# DAU_Kupplung_3phasig_Basisstation_V1_2.net
KiCad netlist of a schematic drawn in EAGLE
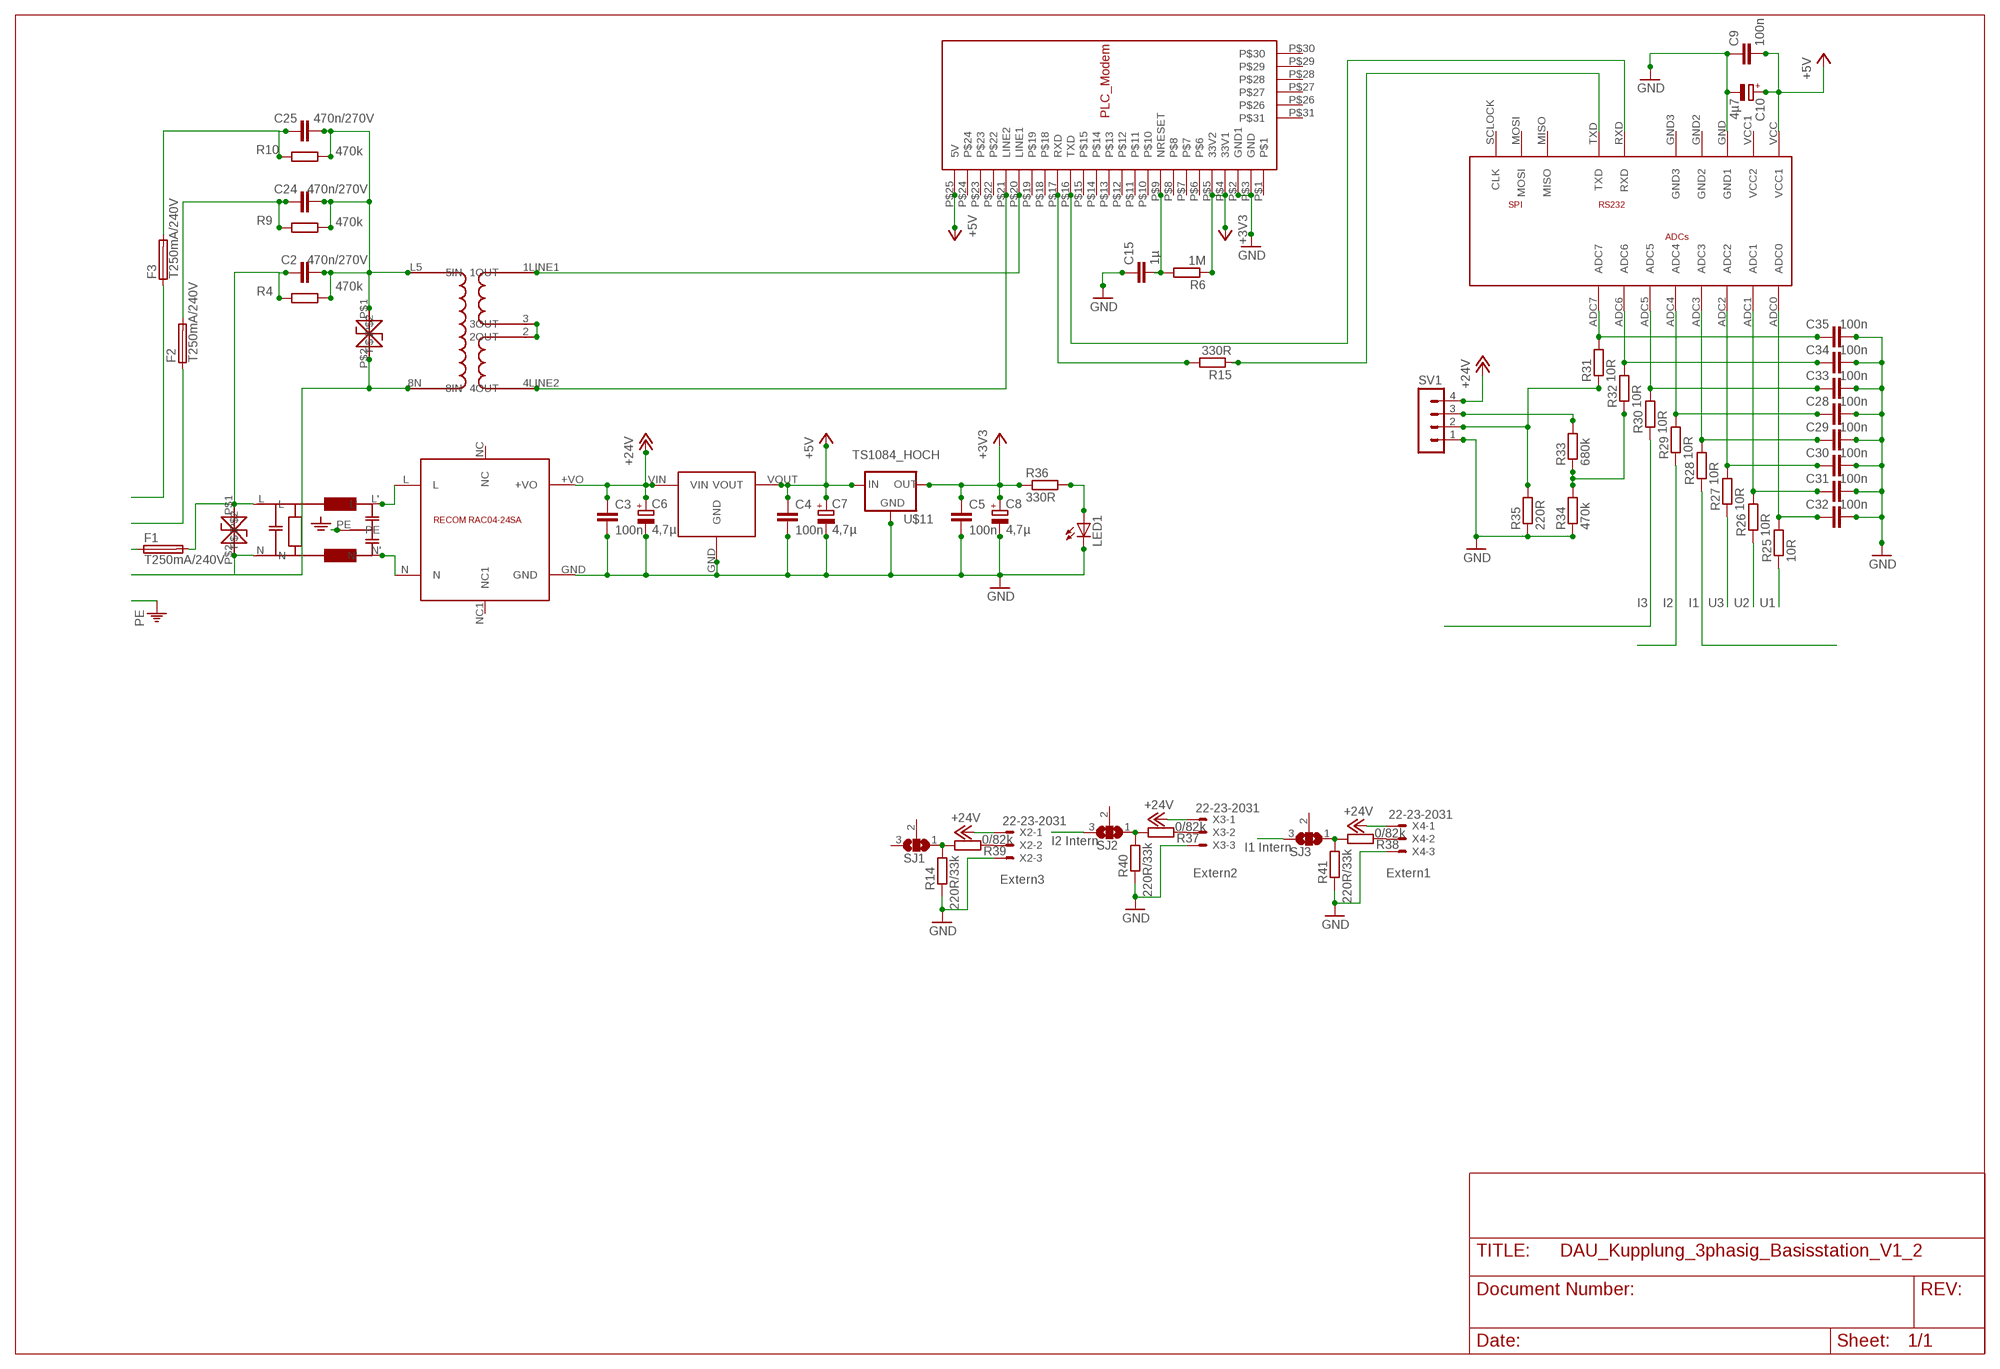
[diagram p0: schematic, sheet 1]

(export (version "E")
  (design (tool "Eeschema 10.0.6"))
  (components
    (comp (ref "C2")
      (value "470n/270V")
      (footprint "eagle-import:C225-087X268")
      (libsource (lib "eagle-import") (part "C-EU225-087X268"))
    )
    (comp (ref "C3")
      (value "100n")
      (footprint "eagle-import:C0805K")
      (libsource (lib "eagle-import") (part "C-EUC0805K"))
    )
    (comp (ref "C4")
      (value "100n")
      (footprint "eagle-import:C0805K")
      (libsource (lib "eagle-import") (part "C-EUC0805K"))
    )
    (comp (ref "C5")
      (value "100n")
      (footprint "eagle-import:C0805K")
      (libsource (lib "eagle-import") (part "C-EUC0805K"))
    )
    (comp (ref "C6")
      (value "4,7µ")
      (footprint "eagle-import:E2,5-6")
      (libsource (lib "eagle-import") (part "resistor_CPOL-EUE2.5-6"))
    )
    (comp (ref "C7")
      (value "4,7µ")
      (footprint "eagle-import:E2,5-6")
      (libsource (lib "eagle-import") (part "resistor_CPOL-EUE2.5-6"))
    )
    (comp (ref "C8")
      (value "4,7µ")
      (footprint "eagle-import:E2,5-6")
      (libsource (lib "eagle-import") (part "resistor_CPOL-EUE2.5-6"))
    )
    (comp (ref "C9")
      (value "100n")
      (footprint "eagle-import:C0805K")
      (libsource (lib "eagle-import") (part "C-EUC0805K"))
    )
    (comp (ref "C10")
      (value "4µ7")
      (footprint "eagle-import:E2,5-6E")
      (libsource (lib "eagle-import") (part "CPOL-EUE2,5-6E"))
    )
    (comp (ref "C15")
      (value "1µ")
      (footprint "eagle-import:C0805K")
      (libsource (lib "eagle-import") (part "C-EUC0805K"))
    )
    (comp (ref "C24")
      (value "470n/270V")
      (footprint "eagle-import:C225-087X268")
      (libsource (lib "eagle-import") (part "C-EU225-087X268"))
    )
    (comp (ref "C25")
      (value "470n/270V")
      (footprint "eagle-import:C225-087X268")
      (libsource (lib "eagle-import") (part "C-EU225-087X268"))
    )
    (comp (ref "C28")
      (value "100n")
      (footprint "eagle-import:C0805K")
      (libsource (lib "eagle-import") (part "C-EUC0805K"))
    )
    (comp (ref "C29")
      (value "100n")
      (footprint "eagle-import:C0805K")
      (libsource (lib "eagle-import") (part "C-EUC0805K"))
    )
    (comp (ref "C30")
      (value "100n")
      (footprint "eagle-import:C0805K")
      (libsource (lib "eagle-import") (part "C-EUC0805K"))
    )
    (comp (ref "C31")
      (value "100n")
      (footprint "eagle-import:C0805K")
      (libsource (lib "eagle-import") (part "C-EUC0805K"))
    )
    (comp (ref "C32")
      (value "100n")
      (footprint "eagle-import:C0805K")
      (libsource (lib "eagle-import") (part "C-EUC0805K"))
    )
    (comp (ref "C33")
      (value "100n")
      (footprint "eagle-import:C0805K")
      (libsource (lib "eagle-import") (part "C-EUC0805K"))
    )
    (comp (ref "C34")
      (value "100n")
      (footprint "eagle-import:C0805K")
      (libsource (lib "eagle-import") (part "C-EUC0805K"))
    )
    (comp (ref "C35")
      (value "100n")
      (footprint "eagle-import:C0805K")
      (libsource (lib "eagle-import") (part "C-EUC0805K"))
    )
    (comp (ref "F1")
      (value "T250mA/240V")
      (footprint "eagle-import:TR5")
      (libsource (lib "eagle-import") (part "TR5"))
    )
    (comp (ref "F2")
      (value "T250mA/240V")
      (footprint "eagle-import:TR5")
      (fields (field (name "OC_FARNELL") "unknown") (field (name "OC_NEWARK") "unknown"))
      (libsource (lib "eagle-import") (part "TR5"))
    )
    (comp (ref "F3")
      (value "T250mA/240V")
      (footprint "eagle-import:TR5")
      (fields (field (name "OC_FARNELL") "unknown") (field (name "OC_NEWARK") "unknown"))
      (libsource (lib "eagle-import") (part "TR5"))
    )
    (comp (ref "LED1")
      (value "LEDSQR2X5")
      (footprint "eagle-import:LED2X5")
      (libsource (lib "eagle-import") (part "LEDSQR2X5"))
    )
    (comp (ref "P6KE300CA")
      (value "P6KE300CA")
      (footprint "eagle-import:TSV")
      (libsource (lib "eagle-import") (part "TSV"))
    )
    (comp (ref "R4")
      (value "470k")
      (footprint "eagle-import:0204_7")
      (libsource (lib "eagle-import") (part "R-EU_0204/7"))
    )
    (comp (ref "R6")
      (value "1M")
      (footprint "eagle-import:R0805")
      (libsource (lib "eagle-import") (part "R-EU_R0805"))
    )
    (comp (ref "R9")
      (value "470k")
      (footprint "eagle-import:0204_7")
      (libsource (lib "eagle-import") (part "R-EU_0204/7"))
    )
    (comp (ref "R10")
      (value "470k")
      (footprint "eagle-import:0204_7")
      (libsource (lib "eagle-import") (part "R-EU_0204/7"))
    )
    (comp (ref "R14")
      (value "220R/33k")
      (footprint "eagle-import:R0805")
      (libsource (lib "eagle-import") (part "R-EU_R0805"))
    )
    (comp (ref "R15")
      (value "330R")
      (footprint "eagle-import:R0805")
      (libsource (lib "eagle-import") (part "R-EU_R0805"))
    )
    (comp (ref "R25")
      (value "10R")
      (footprint "eagle-import:R0805")
      (libsource (lib "eagle-import") (part "R-EU_R0805"))
    )
    (comp (ref "R26")
      (value "10R")
      (footprint "eagle-import:R0805")
      (libsource (lib "eagle-import") (part "R-EU_R0805"))
    )
    (comp (ref "R27")
      (value "10R")
      (footprint "eagle-import:R0805")
      (libsource (lib "eagle-import") (part "R-EU_R0805"))
    )
    (comp (ref "R28")
      (value "10R")
      (footprint "eagle-import:R0805")
      (libsource (lib "eagle-import") (part "R-EU_R0805"))
    )
    (comp (ref "R29")
      (value "10R")
      (footprint "eagle-import:R0805")
      (libsource (lib "eagle-import") (part "R-EU_R0805"))
    )
    (comp (ref "R30")
      (value "10R")
      (footprint "eagle-import:R0805")
      (libsource (lib "eagle-import") (part "R-EU_R0805"))
    )
    (comp (ref "R31")
      (value "10R")
      (footprint "eagle-import:R0805")
      (libsource (lib "eagle-import") (part "R-EU_R0805"))
    )
    (comp (ref "R32")
      (value "10R")
      (footprint "eagle-import:R0805")
      (libsource (lib "eagle-import") (part "R-EU_R0805"))
    )
    (comp (ref "R33")
      (value "680k")
      (footprint "eagle-import:R0805")
      (libsource (lib "eagle-import") (part "R-EU_R0805"))
    )
    (comp (ref "R34")
      (value "470k")
      (footprint "eagle-import:R0805")
      (libsource (lib "eagle-import") (part "R-EU_R0805"))
    )
    (comp (ref "R35")
      (value "220R")
      (footprint "eagle-import:R0805")
      (libsource (lib "eagle-import") (part "R-EU_R0805"))
    )
    (comp (ref "R36")
      (value "330R")
      (footprint "eagle-import:R0805")
      (libsource (lib "eagle-import") (part "R-EU_R0805"))
    )
    (comp (ref "R37")
      (value "0/82k")
      (footprint "eagle-import:R0805")
      (libsource (lib "eagle-import") (part "R-EU_R0805"))
    )
    (comp (ref "R38")
      (value "0/82k")
      (footprint "eagle-import:R0805")
      (libsource (lib "eagle-import") (part "R-EU_R0805"))
    )
    (comp (ref "R39")
      (value "0/82k")
      (footprint "eagle-import:R0805")
      (libsource (lib "eagle-import") (part "R-EU_R0805"))
    )
    (comp (ref "R40")
      (value "220R/33k")
      (footprint "eagle-import:R0805")
      (libsource (lib "eagle-import") (part "R-EU_R0805"))
    )
    (comp (ref "R41")
      (value "220R/33k")
      (footprint "eagle-import:R0805")
      (libsource (lib "eagle-import") (part "R-EU_R0805"))
    )
    (comp (ref "SJ1")
      (value "SJ2WW")
      (footprint "eagle-import:SJ_2W")
      (libsource (lib "eagle-import") (part "SJ2WW"))
    )
    (comp (ref "SJ2")
      (value "SJ2WW")
      (footprint "eagle-import:SJ_2W")
      (libsource (lib "eagle-import") (part "SJ2WW"))
    )
    (comp (ref "SJ3")
      (value "SJ2WW")
      (footprint "eagle-import:SJ_2W")
      (libsource (lib "eagle-import") (part "SJ2WW"))
    )
    (comp (ref "SV1")
      (value "MA04-1")
      (footprint "eagle-import:MA04-1")
      (libsource (lib "eagle-import") (part "MA04-1"))
    )
    (comp (ref "TSV2")
      (value "TSV")
      (footprint "eagle-import:TSV")
      (libsource (lib "eagle-import") (part "TSV"))
    )
    (comp (ref "U$1")
      (value "RECOM_RAC04_24SA")
      (footprint "eagle-import:RAC04_12SA")
      (libsource (lib "eagle-import") (part "RECOM_RAC04_24SA"))
    )
    (comp (ref "U$3")
      (value "ADUC831_MINIMUM")
      (footprint "eagle-import:ADUC_MINIMUM")
      (libsource (lib "eagle-import") (part "ADUC831_MINIMUM"))
    )
    (comp (ref "U$4")
      (value "MODEMSTECKER")
      (footprint "eagle-import:MODEM_FUSS")
      (libsource (lib "eagle-import") (part "MODEMSTECKER"))
    )
    (comp (ref "U$5")
      (value "PLC_UEBERTRAGER_V2")
      (footprint "eagle-import:PLC-UEBERTRAGER_V2")
      (libsource (lib "eagle-import") (part "PLC_UEBERTRAGER_V2"))
    )
    (comp (ref "U$10")
      (value "RECOM_785_05")
      (footprint "eagle-import:RECOM785X")
      (libsource (lib "eagle-import") (part "RECOM_785_05"))
    )
    (comp (ref "U$11")
      (value "TS1084_HOCH")
      (footprint "eagle-import:TS1084_HOCH")
      (libsource (lib "eagle-import") (part "TS1084_HOCH"))
    )
    (comp (ref "U$20")
      (value "NETZFILTER_05_A")
      (footprint "eagle-import:NETZFILTER")
      (libsource (lib "eagle-import") (part "NETZFILTER_05_A"))
    )
    (comp (ref "X2")
      (value "22-23-2031")
      (footprint "eagle-import:22-23-2031")
      (fields (field (name "MF") "MOLEX"))
      (libsource (lib "eagle-import") (part "22-23-2031"))
    )
    (comp (ref "X3")
      (value "22-23-2031")
      (footprint "eagle-import:22-23-2031")
      (fields (field (name "MF") "MOLEX"))
      (libsource (lib "eagle-import") (part "22-23-2031"))
    )
    (comp (ref "X4")
      (value "22-23-2031")
      (footprint "eagle-import:22-23-2031")
      (fields (field (name "MF") "MOLEX"))
      (libsource (lib "eagle-import") (part "22-23-2031"))
    )
  )
  (nets
    (net (code "1") (name "+3V3") (class "Default")
      (node (ref "C5") (pin "1") (pinfunction "1_1") (pintype "passive"))
      (node (ref "C8") (pin "+") (pinfunction "+_+") (pintype "passive"))
      (node (ref "R36") (pin "1") (pinfunction "1_1") (pintype "passive"))
      (node (ref "R6") (pin "1") (pinfunction "1_1") (pintype "passive"))
      (node (ref "U$11") (pin "OUT") (pinfunction "OUT_OUT") (pintype "passive"))
      (node (ref "U$4") (pin "P$4") (pinfunction "33V1_P$4") (pintype "bidirectional"))
      (node (ref "U$4") (pin "P$5") (pinfunction "33V2_P$5") (pintype "bidirectional"))
    )
    (net (code "2") (name "+5V") (class "Default")
      (node (ref "C10") (pin "+") (pinfunction "+_+") (pintype "passive"))
      (node (ref "C4") (pin "1") (pinfunction "1_1") (pintype "passive"))
      (node (ref "C7") (pin "+") (pinfunction "+_+") (pintype "passive"))
      (node (ref "C9") (pin "2") (pinfunction "2_2") (pintype "passive"))
      (node (ref "U$10") (pin "VOUT") (pinfunction "VOUT_VOUT") (pintype "bidirectional"))
      (node (ref "U$11") (pin "IN") (pinfunction "IN_IN") (pintype "input"))
      (node (ref "U$3") (pin "VCC") (pinfunction "VCC1_VCC") (pintype "bidirectional"))
      (node (ref "U$4") (pin "P$25") (pinfunction "5V_P$25") (pintype "bidirectional"))
    )
    (net (code "3") (name "+24V") (class "Default")
      (node (ref "C3") (pin "1") (pinfunction "1_1") (pintype "passive"))
      (node (ref "C6") (pin "+") (pinfunction "+_+") (pintype "passive"))
      (node (ref "SV1") (pin "4") (pinfunction "4_4") (pintype "passive"))
      (node (ref "U$1") (pin "+VO") (pinfunction "+VO_+VO") (pintype "bidirectional"))
      (node (ref "U$10") (pin "VIN") (pinfunction "VIN_VIN") (pintype "bidirectional"))
      (node (ref "X2") (pin "1") (pinfunction "S_1") (pintype "passive"))
      (node (ref "X3") (pin "1") (pinfunction "S_1") (pintype "passive"))
      (node (ref "X4") (pin "1") (pinfunction "S_1") (pintype "passive"))
    )
    (net (code "4") (name "/L1") (class "Default")
      (node (ref "C2") (pin "1") (pinfunction "1_1") (pintype "passive"))
      (node (ref "F1") (pin "2") (pinfunction "2_2") (pintype "passive"))
      (node (ref "P6KE300CA") (pin "P$1") (pinfunction "P$1_P$1") (pintype "bidirectional"))
      (node (ref "R4") (pin "2") (pinfunction "2_2") (pintype "passive"))
      (node (ref "U$20") (pin "L") (pinfunction "L_L") (pintype "bidirectional"))
    )
    (net (code "5") (name "GND") (class "Default")
      (node (ref "C10") (pin "-") (pinfunction "-_-") (pintype "passive"))
      (node (ref "C15") (pin "1") (pinfunction "1_1") (pintype "passive"))
      (node (ref "C28") (pin "2") (pinfunction "2_2") (pintype "passive"))
      (node (ref "C29") (pin "2") (pinfunction "2_2") (pintype "passive"))
      (node (ref "C3") (pin "2") (pinfunction "2_2") (pintype "passive"))
      (node (ref "C30") (pin "2") (pinfunction "2_2") (pintype "passive"))
      (node (ref "C31") (pin "2") (pinfunction "2_2") (pintype "passive"))
      (node (ref "C32") (pin "2") (pinfunction "2_2") (pintype "passive"))
      (node (ref "C33") (pin "2") (pinfunction "2_2") (pintype "passive"))
      (node (ref "C34") (pin "2") (pinfunction "2_2") (pintype "passive"))
      (node (ref "C35") (pin "2") (pinfunction "2_2") (pintype "passive"))
      (node (ref "C4") (pin "2") (pinfunction "2_2") (pintype "passive"))
      (node (ref "C5") (pin "2") (pinfunction "2_2") (pintype "passive"))
      (node (ref "C6") (pin "-") (pinfunction "-_-") (pintype "passive"))
      (node (ref "C7") (pin "-") (pinfunction "-_-") (pintype "passive"))
      (node (ref "C8") (pin "-") (pinfunction "-_-") (pintype "passive"))
      (node (ref "C9") (pin "1") (pinfunction "1_1") (pintype "passive"))
      (node (ref "LED1") (pin "K") (pinfunction "C_K") (pintype "passive"))
      (node (ref "R14") (pin "1") (pinfunction "1_1") (pintype "passive"))
      (node (ref "R34") (pin "1") (pinfunction "1_1") (pintype "passive"))
      (node (ref "R35") (pin "1") (pinfunction "1_1") (pintype "passive"))
      (node (ref "R40") (pin "1") (pinfunction "1_1") (pintype "passive"))
      (node (ref "R41") (pin "1") (pinfunction "1_1") (pintype "passive"))
      (node (ref "SV1") (pin "1") (pinfunction "1_1") (pintype "passive"))
      (node (ref "U$1") (pin "GND") (pinfunction "GND_GND") (pintype "bidirectional"))
      (node (ref "U$10") (pin "GND") (pinfunction "GND_GND") (pintype "bidirectional"))
      (node (ref "U$11") (pin "GND") (pinfunction "GND_GND") (pintype "input"))
      (node (ref "U$3") (pin "GND") (pinfunction "GND1_GND") (pintype "bidirectional"))
      (node (ref "U$4") (pin "P$2") (pinfunction "GND1_P$2") (pintype "bidirectional"))
      (node (ref "U$4") (pin "P$3") (pinfunction "GND_P$3") (pintype "bidirectional"))
      (node (ref "X2") (pin "3") (pinfunction "S_3") (pintype "passive"))
      (node (ref "X3") (pin "3") (pinfunction "S_3") (pintype "passive"))
      (node (ref "X4") (pin "3") (pinfunction "S_3") (pintype "passive"))
    )
    (net (code "6") (name "Net-(C24-Pad1)") (class "Default")
      (node (ref "C24") (pin "1") (pinfunction "1_1") (pintype "passive"))
      (node (ref "F2") (pin "2") (pinfunction "2_2") (pintype "passive"))
      (node (ref "R9") (pin "2") (pinfunction "2_2") (pintype "passive"))
    )
    (net (code "7") (name "Net-(C25-Pad1)") (class "Default")
      (node (ref "C25") (pin "1") (pinfunction "1_1") (pintype "passive"))
      (node (ref "F3") (pin "2") (pinfunction "2_2") (pintype "passive"))
      (node (ref "R10") (pin "2") (pinfunction "2_2") (pintype "passive"))
    )
    (net (code "8") (name "Net-(C28-Pad1)") (class "Default")
      (node (ref "C28") (pin "1") (pinfunction "1_1") (pintype "passive"))
      (node (ref "R29") (pin "2") (pinfunction "2_2") (pintype "passive"))
      (node (ref "U$3") (pin "ADC4") (pinfunction "ADC4_ADC4") (pintype "bidirectional"))
    )
    (net (code "9") (name "Net-(C29-Pad1)") (class "Default")
      (node (ref "C29") (pin "1") (pinfunction "1_1") (pintype "passive"))
      (node (ref "R28") (pin "2") (pinfunction "2_2") (pintype "passive"))
      (node (ref "U$3") (pin "ADC3") (pinfunction "ADC3_ADC3") (pintype "bidirectional"))
    )
    (net (code "10") (name "Net-(C30-Pad1)") (class "Default")
      (node (ref "C30") (pin "1") (pinfunction "1_1") (pintype "passive"))
      (node (ref "R27") (pin "2") (pinfunction "2_2") (pintype "passive"))
      (node (ref "U$3") (pin "ADC2") (pinfunction "ADC2_ADC2") (pintype "bidirectional"))
    )
    (net (code "11") (name "Net-(C31-Pad1)") (class "Default")
      (node (ref "C31") (pin "1") (pinfunction "1_1") (pintype "passive"))
      (node (ref "R26") (pin "2") (pinfunction "2_2") (pintype "passive"))
      (node (ref "U$3") (pin "ADC1") (pinfunction "ADC1_ADC1") (pintype "bidirectional"))
    )
    (net (code "12") (name "Net-(C32-Pad1)") (class "Default")
      (node (ref "C32") (pin "1") (pinfunction "1_1") (pintype "passive"))
      (node (ref "R25") (pin "2") (pinfunction "2_2") (pintype "passive"))
      (node (ref "U$3") (pin "ADC0") (pinfunction "ADC0_ADC0") (pintype "bidirectional"))
    )
    (net (code "13") (name "Net-(C33-Pad1)") (class "Default")
      (node (ref "C33") (pin "1") (pinfunction "1_1") (pintype "passive"))
      (node (ref "R30") (pin "2") (pinfunction "2_2") (pintype "passive"))
      (node (ref "U$3") (pin "ADC5") (pinfunction "ADC5_ADC5") (pintype "bidirectional"))
    )
    (net (code "14") (name "Net-(C34-Pad1)") (class "Default")
      (node (ref "C34") (pin "1") (pinfunction "1_1") (pintype "passive"))
      (node (ref "R32") (pin "2") (pinfunction "2_2") (pintype "passive"))
      (node (ref "U$3") (pin "ADC6") (pinfunction "ADC6_ADC6") (pintype "bidirectional"))
    )
    (net (code "15") (name "Net-(C35-Pad1)") (class "Default")
      (node (ref "C35") (pin "1") (pinfunction "1_1") (pintype "passive"))
      (node (ref "R31") (pin "2") (pinfunction "2_2") (pintype "passive"))
      (node (ref "U$3") (pin "ADC7") (pinfunction "ADC7_ADC7") (pintype "bidirectional"))
    )
    (net (code "16") (name "Net-(LED1-PadA)") (class "Default")
      (node (ref "LED1") (pin "A") (pinfunction "A_A") (pintype "passive"))
      (node (ref "R36") (pin "2") (pinfunction "2_2") (pintype "passive"))
    )
    (net (code "17") (name "Net-(R14-Pad2)") (class "Default")
      (node (ref "R14") (pin "2") (pinfunction "2_2") (pintype "passive"))
      (node (ref "R39") (pin "2") (pinfunction "2_2") (pintype "passive"))
      (node (ref "SJ1") (pin "1") (pinfunction "1_1") (pintype "passive"))
    )
    (net (code "18") (name "Net-(R15-Pad1)") (class "Default")
      (node (ref "R15") (pin "1") (pinfunction "1_1") (pintype "passive"))
      (node (ref "U$3") (pin "TXD") (pinfunction "TXD_TXD") (pintype "bidirectional"))
    )
    (net (code "19") (name "Net-(R31-Pad1)") (class "Default")
      (node (ref "R31") (pin "1") (pinfunction "1_1") (pintype "passive"))
      (node (ref "R35") (pin "2") (pinfunction "2_2") (pintype "passive"))
      (node (ref "SV1") (pin "2") (pinfunction "2_2") (pintype "passive"))
    )
    (net (code "20") (name "Net-(R32-Pad1)") (class "Default")
      (node (ref "R32") (pin "1") (pinfunction "1_1") (pintype "passive"))
      (node (ref "R33") (pin "1") (pinfunction "1_1") (pintype "passive"))
      (node (ref "R34") (pin "2") (pinfunction "2_2") (pintype "passive"))
    )
    (net (code "21") (name "Net-(R33-Pad2)") (class "Default")
      (node (ref "R33") (pin "2") (pinfunction "2_2") (pintype "passive"))
      (node (ref "SV1") (pin "3") (pinfunction "3_3") (pintype "passive"))
    )
    (net (code "22") (name "Net-(R37-Pad2)") (class "Default")
      (node (ref "R37") (pin "2") (pinfunction "2_2") (pintype "passive"))
      (node (ref "R40") (pin "2") (pinfunction "2_2") (pintype "passive"))
      (node (ref "SJ2") (pin "1") (pinfunction "1_1") (pintype "passive"))
    )
    (net (code "23") (name "Net-(R38-Pad2)") (class "Default")
      (node (ref "R38") (pin "2") (pinfunction "2_2") (pintype "passive"))
      (node (ref "R41") (pin "2") (pinfunction "2_2") (pintype "passive"))
      (node (ref "SJ3") (pin "1") (pinfunction "1_1") (pintype "passive"))
    )
    (net (code "24") (name "Net-(U$1-PadL)") (class "Default")
      (node (ref "U$1") (pin "L") (pinfunction "L_L") (pintype "bidirectional"))
      (node (ref "U$20") (pin "L'") (pinfunction "L'_L'") (pintype "bidirectional"))
    )
    (net (code "25") (name "Net-(U$1-PadN)") (class "Default")
      (node (ref "U$1") (pin "N") (pinfunction "N_N") (pintype "bidirectional"))
      (node (ref "U$20") (pin "N'") (pinfunction "N'_N'") (pintype "bidirectional"))
    )
    (net (code "26") (name "Net-(U$4-LINE1)") (class "Default")
      (node (ref "U$4") (pin "P$20") (pinfunction "LINE1_P$20") (pintype "bidirectional"))
      (node (ref "U$5") (pin "1LINE1") (pinfunction "1OUT_1LINE1") (pintype "output"))
    )
    (net (code "27") (name "Net-(U$4-LINE2)") (class "Default")
      (node (ref "U$4") (pin "P$21") (pinfunction "LINE2_P$21") (pintype "bidirectional"))
      (node (ref "U$5") (pin "4LINE2") (pinfunction "4OUT_4LINE2") (pintype "output"))
    )
    (net (code "28") (name "Net-(U$4-NRESET)") (class "Default")
      (node (ref "C15") (pin "2") (pinfunction "2_2") (pintype "passive"))
      (node (ref "R6") (pin "2") (pinfunction "2_2") (pintype "passive"))
      (node (ref "U$4") (pin "P$9") (pinfunction "NRESET_P$9") (pintype "bidirectional"))
    )
    (net (code "29") (name "Net-(U$4-RXD)") (class "Default")
      (node (ref "R15") (pin "2") (pinfunction "2_2") (pintype "passive"))
      (node (ref "U$4") (pin "P$17") (pinfunction "RXD_P$17") (pintype "bidirectional"))
    )
    (net (code "30") (name "Net-(U$4-TXD)") (class "Default")
      (node (ref "U$3") (pin "RXD") (pinfunction "RXD_RXD") (pintype "bidirectional"))
      (node (ref "U$4") (pin "P$16") (pinfunction "TXD_P$16") (pintype "bidirectional"))
    )
    (net (code "31") (name "Net-(U$5-2OUT)") (class "Default")
      (node (ref "U$5") (pin "2") (pinfunction "2OUT_2") (pintype "output"))
      (node (ref "U$5") (pin "3") (pinfunction "3OUT_3") (pintype "output"))
    )
    (net (code "32") (name "Net-(U$5-5IN)") (class "Default")
      (node (ref "C2") (pin "2") (pinfunction "2_2") (pintype "passive"))
      (node (ref "C24") (pin "2") (pinfunction "2_2") (pintype "passive"))
      (node (ref "C25") (pin "2") (pinfunction "2_2") (pintype "passive"))
      (node (ref "R10") (pin "1") (pinfunction "1_1") (pintype "passive"))
      (node (ref "R4") (pin "1") (pinfunction "1_1") (pintype "passive"))
      (node (ref "R9") (pin "1") (pinfunction "1_1") (pintype "passive"))
      (node (ref "TSV2") (pin "P$1") (pinfunction "P$1_P$1") (pintype "bidirectional"))
      (node (ref "U$5") (pin "L5") (pinfunction "5IN_L5") (pintype "input"))
    )
    (net (code "33") (name "Net-(U$5-8IN)") (class "Default")
      (node (ref "P6KE300CA") (pin "P$2") (pinfunction "P$2_P$2") (pintype "bidirectional"))
      (node (ref "TSV2") (pin "P$2") (pinfunction "P$2_P$2") (pintype "bidirectional"))
      (node (ref "U$20") (pin "N") (pinfunction "N_N") (pintype "bidirectional"))
      (node (ref "U$5") (pin "8N") (pinfunction "8IN_8N") (pintype "input"))
    )
    (net (code "34") (name "Net-(X2B-S)") (class "Default")
      (node (ref "R39") (pin "1") (pinfunction "1_1") (pintype "passive"))
      (node (ref "X2") (pin "2") (pinfunction "S_2") (pintype "passive"))
    )
    (net (code "35") (name "Net-(X3B-S)") (class "Default")
      (node (ref "R37") (pin "1") (pinfunction "1_1") (pintype "passive"))
      (node (ref "X3") (pin "2") (pinfunction "S_2") (pintype "passive"))
    )
    (net (code "36") (name "Net-(X4B-S)") (class "Default")
      (node (ref "R38") (pin "1") (pinfunction "1_1") (pintype "passive"))
      (node (ref "X4") (pin "2") (pinfunction "S_2") (pintype "passive"))
    )
    (net (code "37") (name "PE") (class "Default")
      (node (ref "U$20") (pin "PE") (pinfunction "PE_PE") (pintype "input"))
    )
    (net (code "38") (name "unconnected-(F1-Pad1)") (class "Default")
      (node (ref "F1") (pin "1") (pinfunction "1_1") (pintype "passive"))
    )
    (net (code "39") (name "unconnected-(F2-Pad1)") (class "Default")
      (node (ref "F2") (pin "1") (pinfunction "1_1") (pintype "passive"))
    )
    (net (code "40") (name "unconnected-(F3-Pad1)") (class "Default")
      (node (ref "F3") (pin "1") (pinfunction "1_1") (pintype "passive"))
    )
    (net (code "41") (name "unconnected-(R25-Pad1)") (class "Default")
      (node (ref "R25") (pin "1") (pinfunction "1_1") (pintype "passive"))
    )
    (net (code "42") (name "unconnected-(R26-Pad1)") (class "Default")
      (node (ref "R26") (pin "1") (pinfunction "1_1") (pintype "passive"))
    )
    (net (code "43") (name "unconnected-(R27-Pad1)") (class "Default")
      (node (ref "R27") (pin "1") (pinfunction "1_1") (pintype "passive"))
    )
    (net (code "44") (name "unconnected-(R28-Pad1)") (class "Default")
      (node (ref "R28") (pin "1") (pinfunction "1_1") (pintype "passive"))
    )
    (net (code "45") (name "unconnected-(R29-Pad1)") (class "Default")
      (node (ref "R29") (pin "1") (pinfunction "1_1") (pintype "passive"))
    )
    (net (code "46") (name "unconnected-(R30-Pad1)") (class "Default")
      (node (ref "R30") (pin "1") (pinfunction "1_1") (pintype "passive"))
    )
    (net (code "47") (name "unconnected-(SJ1-Pad2)") (class "Default")
      (node (ref "SJ1") (pin "2") (pinfunction "2_2") (pintype "passive"))
    )
    (net (code "48") (name "unconnected-(SJ1-Pad3)") (class "Default")
      (node (ref "SJ1") (pin "3") (pinfunction "3_3") (pintype "passive"))
    )
    (net (code "49") (name "unconnected-(SJ2-Pad2)") (class "Default")
      (node (ref "SJ2") (pin "2") (pinfunction "2_2") (pintype "passive"))
    )
    (net (code "50") (name "unconnected-(SJ2-Pad3)") (class "Default")
      (node (ref "SJ2") (pin "3") (pinfunction "3_3") (pintype "passive"))
    )
    (net (code "51") (name "unconnected-(SJ3-Pad2)") (class "Default")
      (node (ref "SJ3") (pin "2") (pinfunction "2_2") (pintype "passive"))
    )
    (net (code "52") (name "unconnected-(SJ3-Pad3)") (class "Default")
      (node (ref "SJ3") (pin "3") (pinfunction "3_3") (pintype "passive"))
    )
    (net (code "53") (name "unconnected-(U$1-PadNC)") (class "Default")
      (node (ref "U$1") (pin "NC") (pinfunction "NC_NC") (pintype "bidirectional"))
    )
    (net (code "54") (name "unconnected-(U$1-PadNC1)") (class "Default")
      (node (ref "U$1") (pin "NC1") (pinfunction "NC1_NC1") (pintype "bidirectional"))
    )
    (net (code "55") (name "unconnected-(U$3-CLK-PadSCLOCK)") (class "Default")
      (node (ref "U$3") (pin "SCLOCK") (pinfunction "CLK_SCLOCK") (pintype "bidirectional"))
    )
    (net (code "56") (name "unconnected-(U$3-PadGND2)") (class "Default")
      (node (ref "U$3") (pin "GND2") (pinfunction "GND2_GND2") (pintype "bidirectional"))
    )
    (net (code "57") (name "unconnected-(U$3-PadGND3)") (class "Default")
      (node (ref "U$3") (pin "GND3") (pinfunction "GND3_GND3") (pintype "bidirectional"))
    )
    (net (code "58") (name "unconnected-(U$3-PadMISO)") (class "Default")
      (node (ref "U$3") (pin "MISO") (pinfunction "MISO_MISO") (pintype "bidirectional"))
    )
    (net (code "59") (name "unconnected-(U$3-PadMOSI)") (class "Default")
      (node (ref "U$3") (pin "MOSI") (pinfunction "MOSI_MOSI") (pintype "bidirectional"))
    )
    (net (code "60") (name "unconnected-(U$3-VCC2-PadVCC1)") (class "Default")
      (node (ref "U$3") (pin "VCC1") (pinfunction "VCC2_VCC1") (pintype "bidirectional"))
    )
    (net (code "61") (name "unconnected-(U$4-PadP$1)") (class "Default")
      (node (ref "U$4") (pin "P$1") (pinfunction "P$1_P$1") (pintype "bidirectional"))
    )
    (net (code "62") (name "unconnected-(U$4-PadP$6)") (class "Default")
      (node (ref "U$4") (pin "P$6") (pinfunction "P$6_P$6") (pintype "bidirectional"))
    )
    (net (code "63") (name "unconnected-(U$4-PadP$7)") (class "Default")
      (node (ref "U$4") (pin "P$7") (pinfunction "P$7_P$7") (pintype "bidirectional"))
    )
    (net (code "64") (name "unconnected-(U$4-PadP$8)") (class "Default")
      (node (ref "U$4") (pin "P$8") (pinfunction "P$8_P$8") (pintype "bidirectional"))
    )
    (net (code "65") (name "unconnected-(U$4-PadP$10)") (class "Default")
      (node (ref "U$4") (pin "P$10") (pinfunction "P$10_P$10") (pintype "bidirectional"))
    )
    (net (code "66") (name "unconnected-(U$4-PadP$11)") (class "Default")
      (node (ref "U$4") (pin "P$11") (pinfunction "P$11_P$11") (pintype "bidirectional"))
    )
    (net (code "67") (name "unconnected-(U$4-PadP$12)") (class "Default")
      (node (ref "U$4") (pin "P$12") (pinfunction "P$12_P$12") (pintype "bidirectional"))
    )
    (net (code "68") (name "unconnected-(U$4-PadP$13)") (class "Default")
      (node (ref "U$4") (pin "P$13") (pinfunction "P$13_P$13") (pintype "bidirectional"))
    )
    (net (code "69") (name "unconnected-(U$4-PadP$14)") (class "Default")
      (node (ref "U$4") (pin "P$14") (pinfunction "P$14_P$14") (pintype "bidirectional"))
    )
    (net (code "70") (name "unconnected-(U$4-PadP$15)") (class "Default")
      (node (ref "U$4") (pin "P$15") (pinfunction "P$15_P$15") (pintype "bidirectional"))
    )
    (net (code "71") (name "unconnected-(U$4-PadP$18)") (class "Default")
      (node (ref "U$4") (pin "P$18") (pinfunction "P$18_P$18") (pintype "bidirectional"))
    )
    (net (code "72") (name "unconnected-(U$4-PadP$19)") (class "Default")
      (node (ref "U$4") (pin "P$19") (pinfunction "P$19_P$19") (pintype "bidirectional"))
    )
    (net (code "73") (name "unconnected-(U$4-PadP$22)") (class "Default")
      (node (ref "U$4") (pin "P$22") (pinfunction "P$22_P$22") (pintype "bidirectional"))
    )
    (net (code "74") (name "unconnected-(U$4-PadP$23)") (class "Default")
      (node (ref "U$4") (pin "P$23") (pinfunction "P$23_P$23") (pintype "bidirectional"))
    )
    (net (code "75") (name "unconnected-(U$4-PadP$24)") (class "Default")
      (node (ref "U$4") (pin "P$24") (pinfunction "P$24_P$24") (pintype "bidirectional"))
    )
    (net (code "76") (name "unconnected-(U$4-PadP$26)") (class "Default")
      (node (ref "U$4") (pin "P$26") (pinfunction "P$26_P$26") (pintype "bidirectional"))
    )
    (net (code "77") (name "unconnected-(U$4-PadP$27)") (class "Default")
      (node (ref "U$4") (pin "P$27") (pinfunction "P$27_P$27") (pintype "bidirectional"))
    )
    (net (code "78") (name "unconnected-(U$4-PadP$28)") (class "Default")
      (node (ref "U$4") (pin "P$28") (pinfunction "P$28_P$28") (pintype "bidirectional"))
    )
    (net (code "79") (name "unconnected-(U$4-PadP$29)") (class "Default")
      (node (ref "U$4") (pin "P$29") (pinfunction "P$29_P$29") (pintype "bidirectional"))
    )
    (net (code "80") (name "unconnected-(U$4-PadP$30)") (class "Default")
      (node (ref "U$4") (pin "P$30") (pinfunction "P$30_P$30") (pintype "bidirectional"))
    )
    (net (code "81") (name "unconnected-(U$4-PadP$31)") (class "Default")
      (node (ref "U$4") (pin "P$31") (pinfunction "P$31_P$31") (pintype "bidirectional"))
    )
  )
)
